# bd950_interface.net
KiCad netlist of a schematic drawn in EAGLE
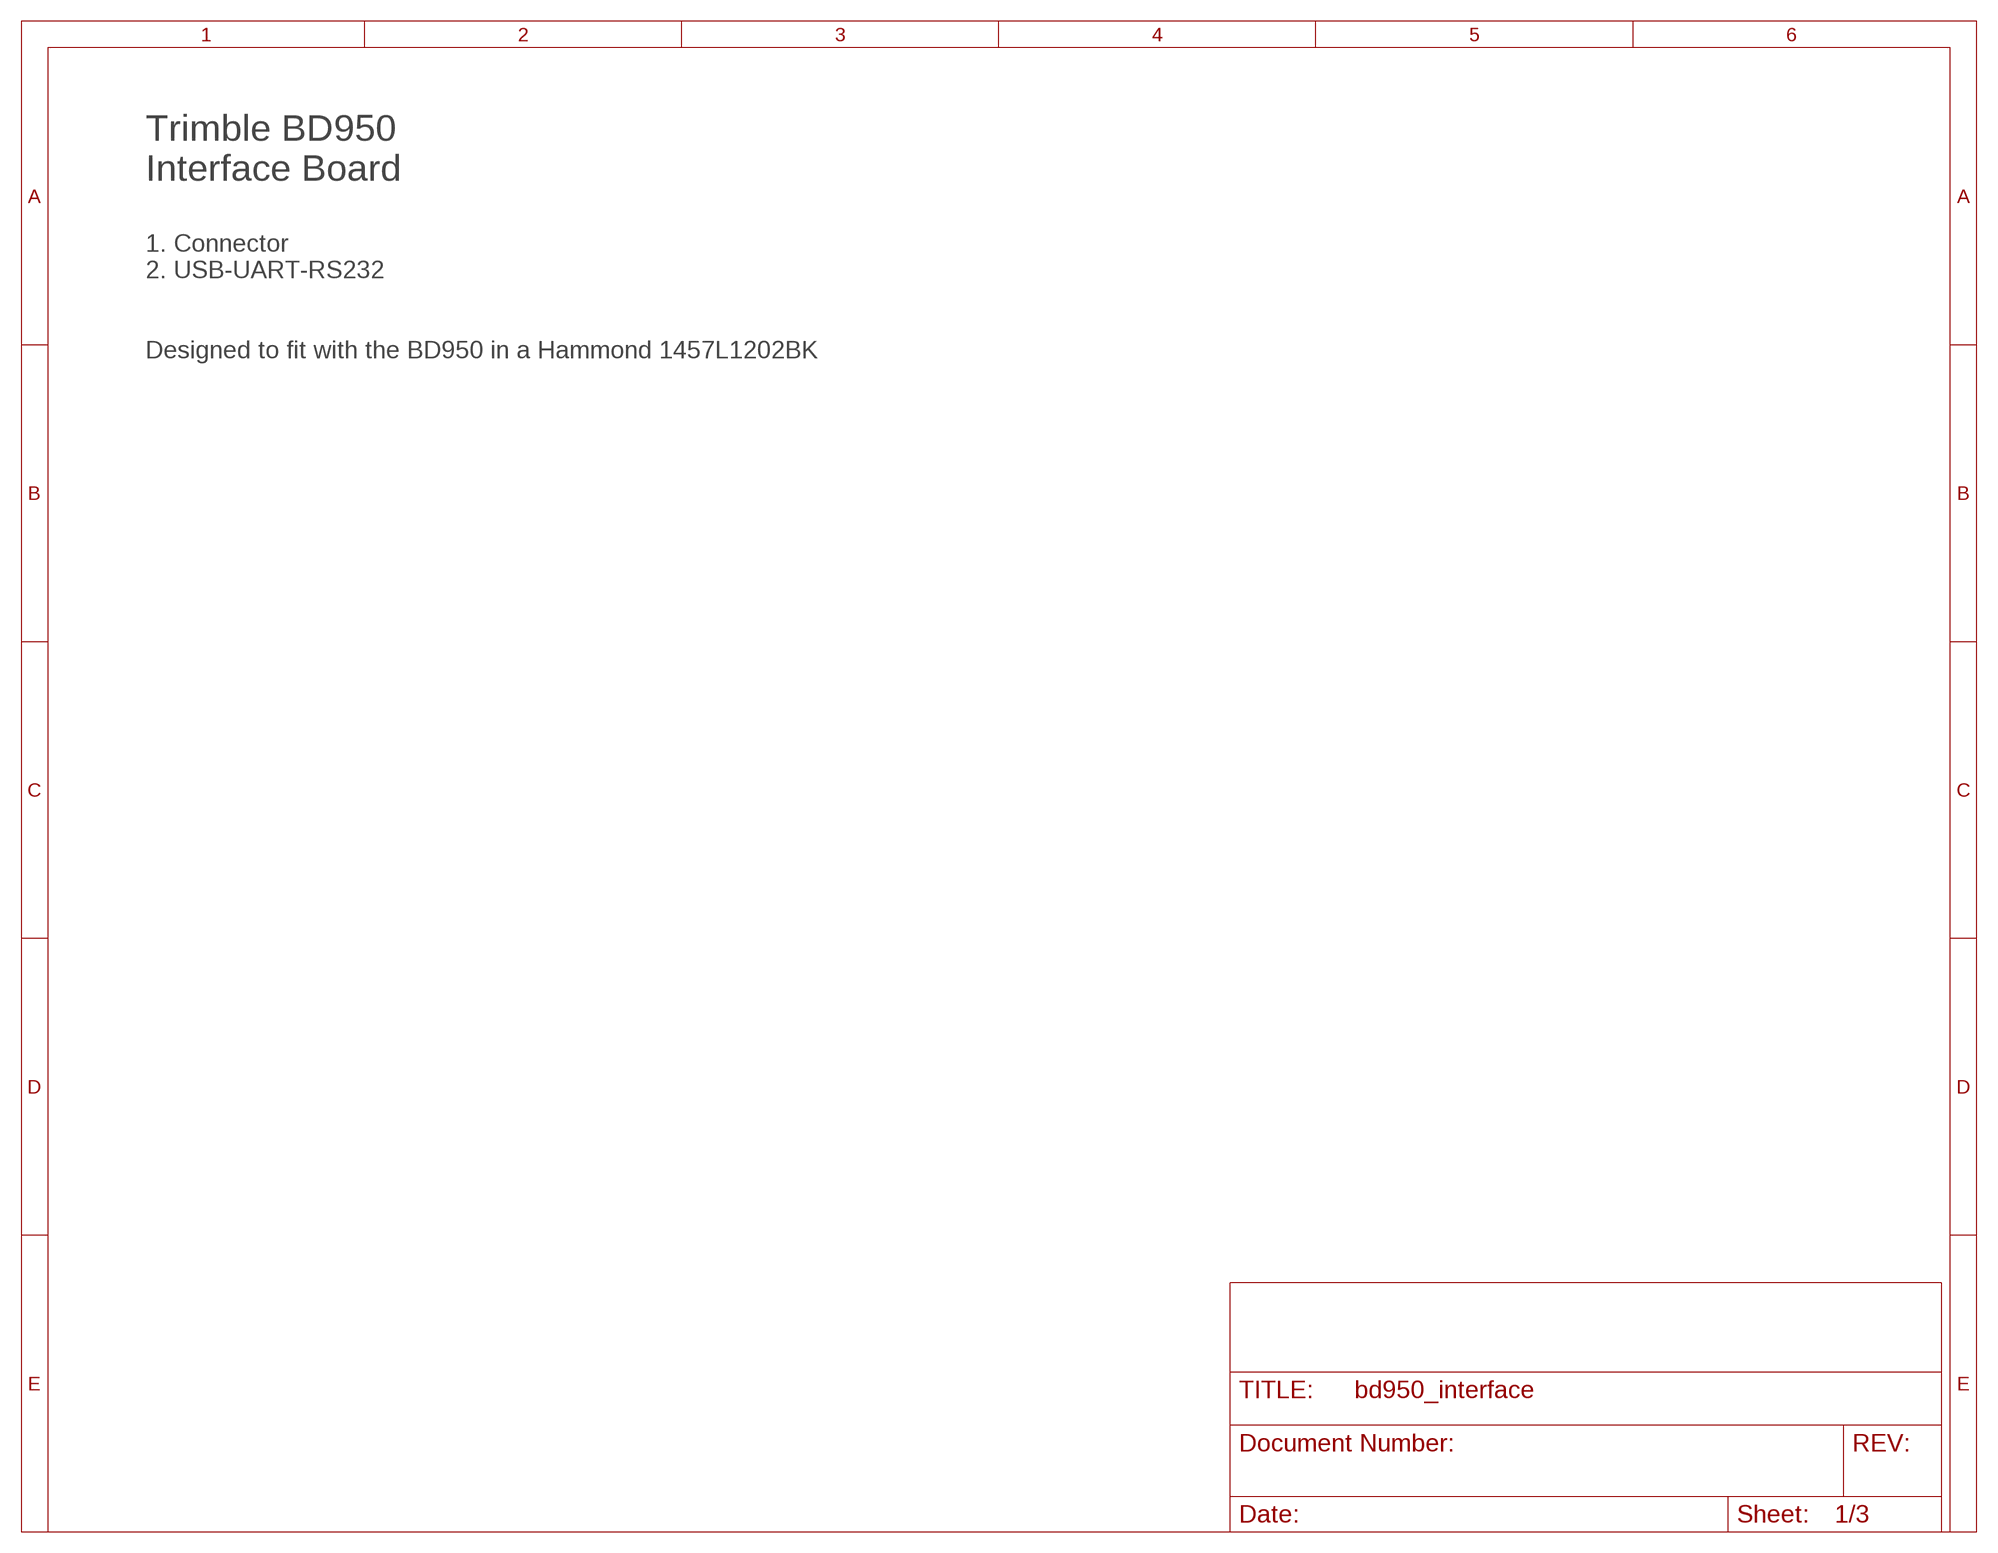
[diagram p0: schematic, sheet 1]
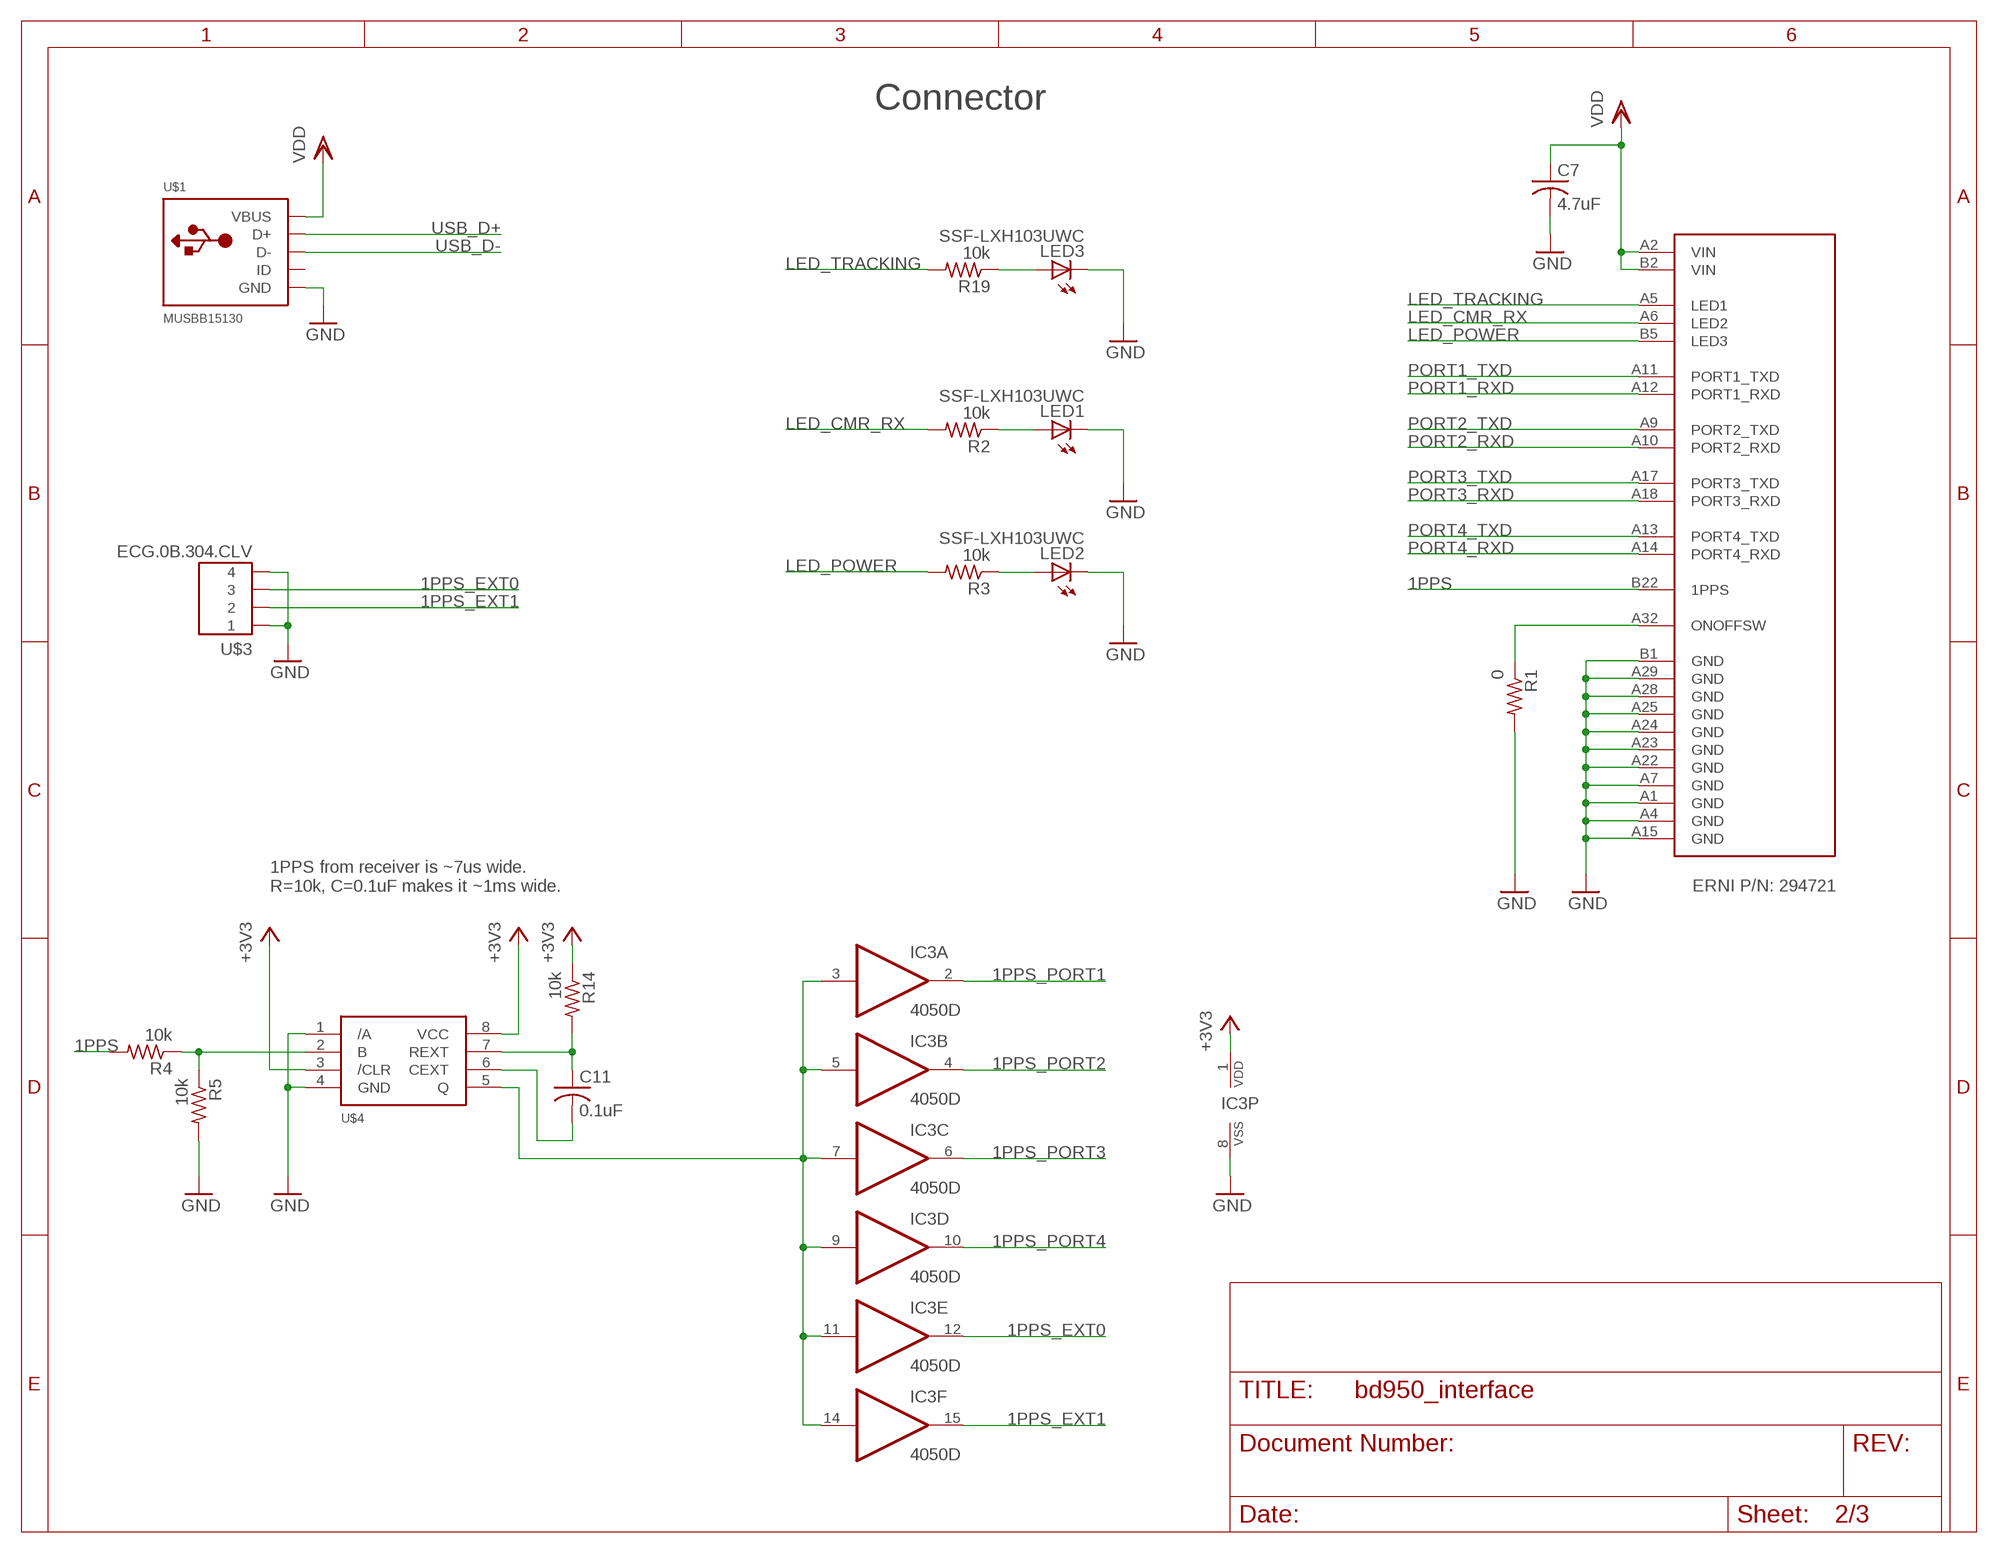
[diagram p1: schematic, sheet 2]
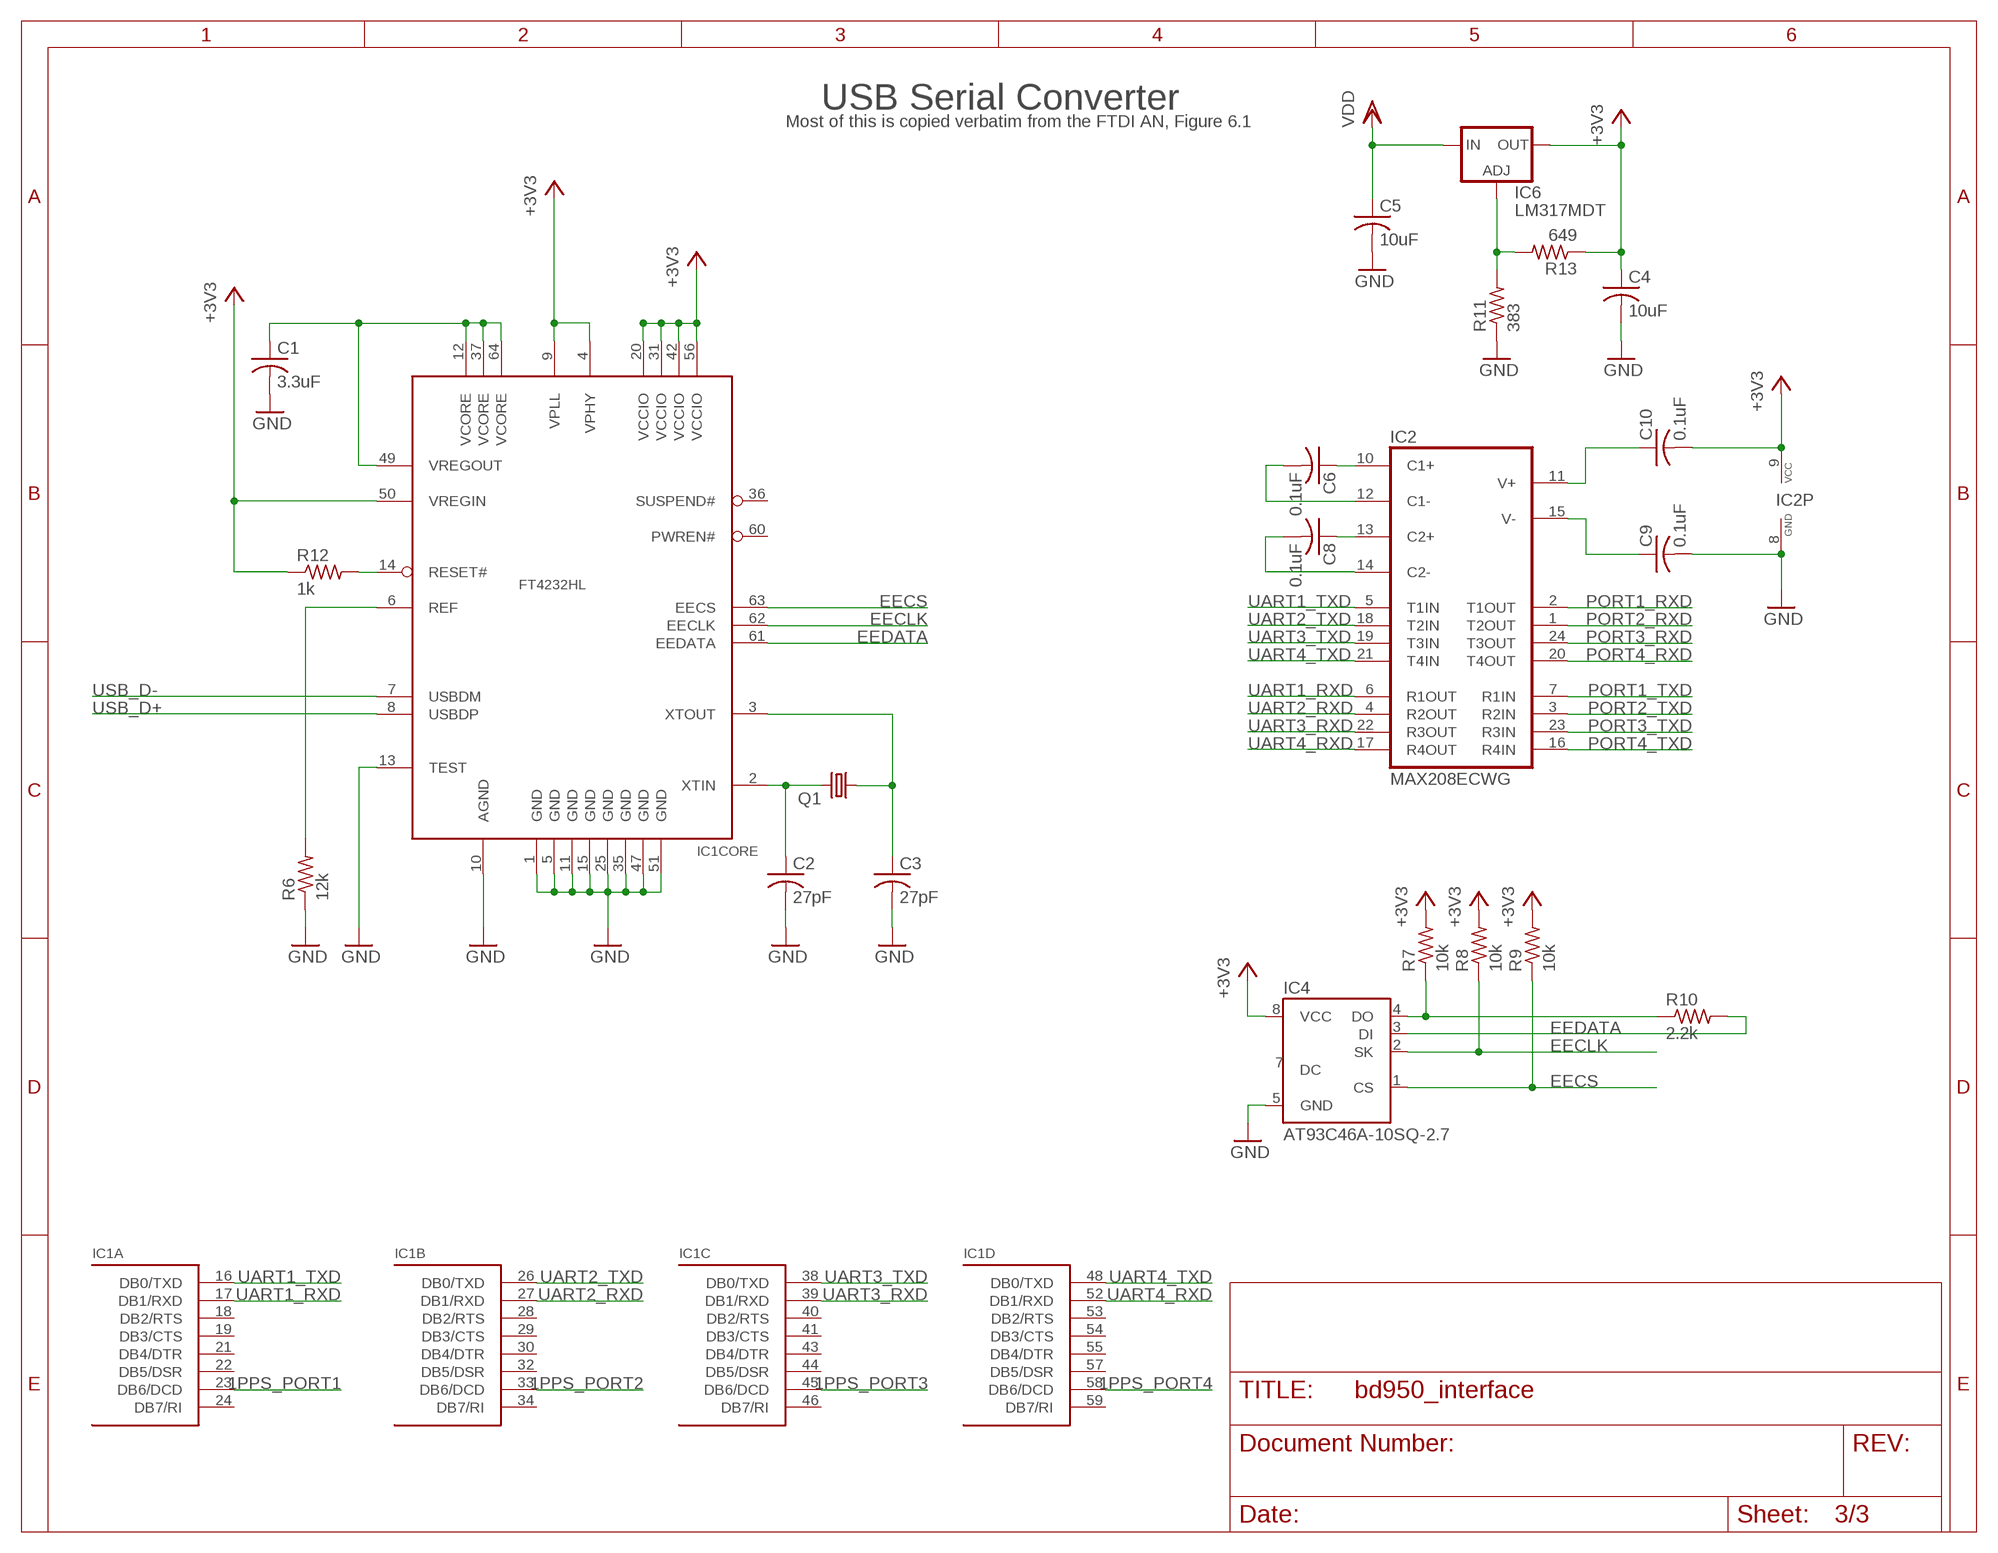
[diagram p2: schematic, sheet 3]

(export (version "E")
  (design (tool "Eeschema 10.0.6"))
  (components
    (comp (ref "C7")
      (value "4.7uF")
      (footprint "eagle-import:C0805")
      (libsource (lib "eagle-import") (part "C-USC0805"))
    )
    (comp (ref "C11")
      (value "0.1uF")
      (footprint "eagle-import:C0603")
      (libsource (lib "eagle-import") (part "C-USC0603"))
    )
    (comp (ref "IC3")
      (value "4050D")
      (footprint "eagle-import:SO16")
      (libsource (lib "eagle-import") (part "4050D"))
    )
    (comp (ref "LED1")
      (value "SSF-LXH103UWC")
      (footprint "eagle-import:CHIP-LED0603")
      (libsource (lib "eagle-import") (part "LEDCHIP-LED0603"))
    )
    (comp (ref "LED2")
      (value "SSF-LXH103UWC")
      (footprint "eagle-import:CHIP-LED0603")
      (libsource (lib "eagle-import") (part "LEDCHIP-LED0603"))
    )
    (comp (ref "LED3")
      (value "SSF-LXH103UWC")
      (footprint "eagle-import:CHIP-LED0603")
      (libsource (lib "eagle-import") (part "LEDCHIP-LED0603"))
    )
    (comp (ref "R1")
      (value "0")
      (footprint "eagle-import:R0603")
      (libsource (lib "eagle-import") (part "R-US_R0603"))
    )
    (comp (ref "R2")
      (value "10k")
      (footprint "eagle-import:R0603")
      (libsource (lib "eagle-import") (part "R-US_R0603"))
    )
    (comp (ref "R3")
      (value "10k")
      (footprint "eagle-import:R0603")
      (libsource (lib "eagle-import") (part "R-US_R0603"))
    )
    (comp (ref "R4")
      (value "10k")
      (footprint "eagle-import:R0603")
      (libsource (lib "eagle-import") (part "R-US_R0603"))
    )
    (comp (ref "R5")
      (value "10k")
      (footprint "eagle-import:R0603")
      (libsource (lib "eagle-import") (part "R-US_R0603"))
    )
    (comp (ref "R14")
      (value "10k")
      (footprint "eagle-import:R0603")
      (libsource (lib "eagle-import") (part "R-US_R0603"))
    )
    (comp (ref "R19")
      (value "10k")
      (footprint "eagle-import:R0603")
      (libsource (lib "eagle-import") (part "R-US_R0603"))
    )
    (comp (ref "U$1")
      (value "MUSBB15130")
      (footprint "eagle-import:MUSBB15130")
      (libsource (lib "eagle-import") (part "MUSBB15130"))
    )
    (comp (ref "U$2")
      (value "294721")
      (footprint "eagle-import:TRIMBLE_BD950")
      (libsource (lib "eagle-import") (part "TRIMBLE_BD950"))
    )
    (comp (ref "U$3")
      (value "ECG.0B.304.CLV")
      (footprint "eagle-import:ECG.0B.CLV")
      (libsource (lib "eagle-import") (part "ECG.0B.CLV"))
    )
    (comp (ref "U$4")
      (value "SN74LVC1G123")
      (footprint "eagle-import:DCU_(R-PDSO-G8)")
      (libsource (lib "eagle-import") (part "SN74LVC1G123"))
    )
    (comp (ref "C1")
      (value "3.3uF")
      (footprint "eagle-import:C0603")
      (libsource (lib "eagle-import") (part "C-USC0603"))
    )
    (comp (ref "C2")
      (value "27pF")
      (footprint "eagle-import:C0603")
      (libsource (lib "eagle-import") (part "C-USC0603"))
    )
    (comp (ref "C3")
      (value "27pF")
      (footprint "eagle-import:C0603")
      (libsource (lib "eagle-import") (part "C-USC0603"))
    )
    (comp (ref "C4")
      (value "10uF")
      (footprint "eagle-import:C0805")
      (libsource (lib "eagle-import") (part "C-USC0805"))
    )
    (comp (ref "C5")
      (value "10uF")
      (footprint "eagle-import:C0805")
      (libsource (lib "eagle-import") (part "C-USC0805"))
    )
    (comp (ref "C6")
      (value "0.1uF")
      (footprint "eagle-import:C0603")
      (libsource (lib "eagle-import") (part "C-USC0603"))
    )
    (comp (ref "C8")
      (value "0.1uF")
      (footprint "eagle-import:C0603")
      (libsource (lib "eagle-import") (part "C-USC0603"))
    )
    (comp (ref "C9")
      (value "0.1uF")
      (footprint "eagle-import:C0603")
      (libsource (lib "eagle-import") (part "C-USC0603"))
    )
    (comp (ref "C10")
      (value "0.1uF")
      (footprint "eagle-import:C0603")
      (libsource (lib "eagle-import") (part "C-USC0603"))
    )
    (comp (ref "IC1")
      (value "FT4232HL")
      (footprint "eagle-import:LQFP64")
      (libsource (lib "eagle-import") (part "FT4232HL"))
    )
    (comp (ref "IC2")
      (value "MAX208ECWG")
      (footprint "eagle-import:SO24L")
      (fields (field (name "MPN") "MAX208ECWG+"))
      (libsource (lib "eagle-import") (part "MAX208ECWG"))
    )
    (comp (ref "IC4")
      (value "AT93C46A-10SQ-2.7")
      (footprint "eagle-import:SOIC8")
      (fields (field (name "MPN") "AT93C46DN-SH-B"))
      (libsource (lib "eagle-import") (part "AT93C46A-10?Q-2.7S"))
    )
    (comp (ref "IC6")
      (value "LM317MDT")
      (footprint "eagle-import:DPACK")
      (libsource (lib "eagle-import") (part "LM317?MDT"))
    )
    (comp (ref "Q1")
      (value "CRYSTALHC49S")
      (footprint "eagle-import:HC49_S")
      (libsource (lib "eagle-import") (part "CRYSTALHC49S"))
    )
    (comp (ref "R6")
      (value "12k")
      (footprint "eagle-import:R0603")
      (libsource (lib "eagle-import") (part "resistor_R-US_R0603"))
    )
    (comp (ref "R7")
      (value "10k")
      (footprint "eagle-import:R0603")
      (libsource (lib "eagle-import") (part "resistor_R-US_R0603"))
    )
    (comp (ref "R8")
      (value "10k")
      (footprint "eagle-import:R0603")
      (libsource (lib "eagle-import") (part "resistor_R-US_R0603"))
    )
    (comp (ref "R9")
      (value "10k")
      (footprint "eagle-import:R0603")
      (libsource (lib "eagle-import") (part "resistor_R-US_R0603"))
    )
    (comp (ref "R10")
      (value "2.2k")
      (footprint "eagle-import:R0603")
      (libsource (lib "eagle-import") (part "resistor_R-US_R0603"))
    )
    (comp (ref "R11")
      (value "383")
      (footprint "eagle-import:R0603")
      (libsource (lib "eagle-import") (part "resistor_R-US_R0603"))
    )
    (comp (ref "R12")
      (value "1k")
      (footprint "eagle-import:R0603")
      (libsource (lib "eagle-import") (part "resistor_R-US_R0603"))
    )
    (comp (ref "R13")
      (value "649")
      (footprint "eagle-import:R0603")
      (libsource (lib "eagle-import") (part "resistor_R-US_R0603"))
    )
  )
  (nets
    (net (code "1") (name "+3V3") (class "Default")
      (node (ref "C10") (pin "2") (pinfunction "2_2") (pintype "passive"))
      (node (ref "C4") (pin "1") (pinfunction "1_1") (pintype "passive"))
      (node (ref "IC1") (pin "20") (pinfunction "VCCIO_20") (pintype "power_in"))
      (node (ref "IC1") (pin "31") (pinfunction "VCCIO_31") (pintype "power_in"))
      (node (ref "IC1") (pin "4") (pinfunction "VPHY_4") (pintype "power_in"))
      (node (ref "IC1") (pin "42") (pinfunction "VCCIO_42") (pintype "power_in"))
      (node (ref "IC1") (pin "50") (pinfunction "VREGIN_50") (pintype "bidirectional"))
      (node (ref "IC1") (pin "56") (pinfunction "VCCIO_56") (pintype "power_in"))
      (node (ref "IC1") (pin "9") (pinfunction "VPLL_9") (pintype "power_in"))
      (node (ref "IC2") (pin "9") (pinfunction "VCC_9") (pintype "power_in"))
      (node (ref "IC3") (pin "1") (pinfunction "VDD_1") (pintype "power_in"))
      (node (ref "IC4") (pin "8") (pinfunction "VCC_8") (pintype "power_in"))
      (node (ref "IC6") (pin "4") (pinfunction "OUT_4") (pintype "passive"))
      (node (ref "R12") (pin "1") (pinfunction "1_1") (pintype "passive"))
      (node (ref "R13") (pin "1") (pinfunction "1_1") (pintype "passive"))
      (node (ref "R14") (pin "1") (pinfunction "1_1") (pintype "passive"))
      (node (ref "R7") (pin "2") (pinfunction "2_2") (pintype "passive"))
      (node (ref "R8") (pin "2") (pinfunction "2_2") (pintype "passive"))
      (node (ref "R9") (pin "2") (pinfunction "2_2") (pintype "passive"))
      (node (ref "U$4") (pin "3") (pinfunction "/CLR_3") (pintype "bidirectional"))
      (node (ref "U$4") (pin "8") (pinfunction "VCC_8") (pintype "bidirectional"))
    )
    (net (code "2") (name "1PPS") (class "Default")
      (node (ref "R4") (pin "2") (pinfunction "2_2") (pintype "passive"))
      (node (ref "U$2") (pin "B22") (pinfunction "1PPS_B22") (pintype "bidirectional"))
    )
    (net (code "3") (name "1PPS_EXT0") (class "Default")
      (node (ref "IC3") (pin "12") (pinfunction "O_12") (pintype "output"))
      (node (ref "U$3") (pin "P$4") (pinfunction "3_P$4") (pintype "passive"))
    )
    (net (code "4") (name "1PPS_EXT1") (class "Default")
      (node (ref "IC3") (pin "15") (pinfunction "O_15") (pintype "output"))
      (node (ref "U$3") (pin "P$3") (pinfunction "2_P$3") (pintype "passive"))
    )
    (net (code "5") (name "1PPS_PORT1") (class "Default")
      (node (ref "IC1") (pin "23") (pinfunction "DB6/DCD_23") (pintype "bidirectional"))
      (node (ref "IC3") (pin "2") (pinfunction "O_2") (pintype "output"))
    )
    (net (code "6") (name "1PPS_PORT2") (class "Default")
      (node (ref "IC1") (pin "33") (pinfunction "DB6/DCD_33") (pintype "bidirectional"))
      (node (ref "IC3") (pin "4") (pinfunction "O_4") (pintype "output"))
    )
    (net (code "7") (name "1PPS_PORT3") (class "Default")
      (node (ref "IC1") (pin "45") (pinfunction "DB6/DCD_45") (pintype "bidirectional"))
      (node (ref "IC3") (pin "6") (pinfunction "O_6") (pintype "output"))
    )
    (net (code "8") (name "1PPS_PORT4") (class "Default")
      (node (ref "IC1") (pin "58") (pinfunction "DB6/DCD_58") (pintype "bidirectional"))
      (node (ref "IC3") (pin "10") (pinfunction "O_10") (pintype "output"))
    )
    (net (code "9") (name "EECLK") (class "Default")
      (node (ref "IC1") (pin "62") (pinfunction "EECLK_62") (pintype "output"))
      (node (ref "IC4") (pin "2") (pinfunction "SK_2") (pintype "input"))
      (node (ref "R8") (pin "1") (pinfunction "1_1") (pintype "passive"))
    )
    (net (code "10") (name "EECS") (class "Default")
      (node (ref "IC1") (pin "63") (pinfunction "EECS_63") (pintype "bidirectional"))
      (node (ref "IC4") (pin "1") (pinfunction "CS_1") (pintype "input"))
      (node (ref "R9") (pin "1") (pinfunction "1_1") (pintype "passive"))
    )
    (net (code "11") (name "EEDATA") (class "Default")
      (node (ref "IC1") (pin "61") (pinfunction "EEDATA_61") (pintype "bidirectional"))
      (node (ref "IC4") (pin "3") (pinfunction "DI_3") (pintype "input"))
      (node (ref "R10") (pin "2") (pinfunction "2_2") (pintype "passive"))
    )
    (net (code "12") (name "GND") (class "Default")
      (node (ref "C1") (pin "2") (pinfunction "2_2") (pintype "passive"))
      (node (ref "C2") (pin "2") (pinfunction "2_2") (pintype "passive"))
      (node (ref "C3") (pin "2") (pinfunction "2_2") (pintype "passive"))
      (node (ref "C4") (pin "2") (pinfunction "2_2") (pintype "passive"))
      (node (ref "C5") (pin "2") (pinfunction "2_2") (pintype "passive"))
      (node (ref "C7") (pin "2") (pinfunction "2_2") (pintype "passive"))
      (node (ref "C9") (pin "2") (pinfunction "2_2") (pintype "passive"))
      (node (ref "IC1") (pin "1") (pinfunction "GND_1") (pintype "power_in"))
      (node (ref "IC1") (pin "10") (pinfunction "AGND_10") (pintype "power_in"))
      (node (ref "IC1") (pin "11") (pinfunction "GND_11") (pintype "power_in"))
      (node (ref "IC1") (pin "13") (pinfunction "TEST_13") (pintype "input"))
      (node (ref "IC1") (pin "15") (pinfunction "GND_15") (pintype "power_in"))
      (node (ref "IC1") (pin "25") (pinfunction "GND_25") (pintype "power_in"))
      (node (ref "IC1") (pin "35") (pinfunction "GND_35") (pintype "power_in"))
      (node (ref "IC1") (pin "47") (pinfunction "GND_47") (pintype "power_in"))
      (node (ref "IC1") (pin "5") (pinfunction "GND_5") (pintype "power_in"))
      (node (ref "IC1") (pin "51") (pinfunction "GND_51") (pintype "power_in"))
      (node (ref "IC2") (pin "8") (pinfunction "GND_8") (pintype "power_in"))
      (node (ref "IC3") (pin "8") (pinfunction "VSS_8") (pintype "power_in"))
      (node (ref "IC4") (pin "5") (pinfunction "GND_5") (pintype "power_in"))
      (node (ref "LED1") (pin "C") (pinfunction "C_C") (pintype "passive"))
      (node (ref "LED2") (pin "C") (pinfunction "C_C") (pintype "passive"))
      (node (ref "LED3") (pin "C") (pinfunction "C_C") (pintype "passive"))
      (node (ref "R1") (pin "2") (pinfunction "2_2") (pintype "passive"))
      (node (ref "R11") (pin "1") (pinfunction "1_1") (pintype "passive"))
      (node (ref "R5") (pin "2") (pinfunction "2_2") (pintype "passive"))
      (node (ref "R6") (pin "1") (pinfunction "1_1") (pintype "passive"))
      (node (ref "U$1") (pin "5") (pinfunction "GND_5") (pintype "power_in"))
      (node (ref "U$2") (pin "A1") (pinfunction "GND_A1") (pintype "bidirectional"))
      (node (ref "U$2") (pin "A15") (pinfunction "GND_A15") (pintype "bidirectional"))
      (node (ref "U$2") (pin "A22") (pinfunction "GND_A22") (pintype "bidirectional"))
      (node (ref "U$2") (pin "A23") (pinfunction "GND_A23") (pintype "bidirectional"))
      (node (ref "U$2") (pin "A24") (pinfunction "GND_A24") (pintype "bidirectional"))
      (node (ref "U$2") (pin "A25") (pinfunction "GND_A25") (pintype "bidirectional"))
      (node (ref "U$2") (pin "A28") (pinfunction "GND_A28") (pintype "bidirectional"))
      (node (ref "U$2") (pin "A29") (pinfunction "GND_A29") (pintype "bidirectional"))
      (node (ref "U$2") (pin "A4") (pinfunction "GND_A4") (pintype "bidirectional"))
      (node (ref "U$2") (pin "A7") (pinfunction "GND_A7") (pintype "bidirectional"))
      (node (ref "U$2") (pin "B1") (pinfunction "GND_B1") (pintype "bidirectional"))
      (node (ref "U$3") (pin "P$1") (pinfunction "4_P$1") (pintype "passive"))
      (node (ref "U$3") (pin "P$2") (pinfunction "1_P$2") (pintype "passive"))
      (node (ref "U$4") (pin "1") (pinfunction "/A_1") (pintype "bidirectional"))
      (node (ref "U$4") (pin "4") (pinfunction "GND_4") (pintype "bidirectional"))
    )
    (net (code "13") (name "LED_CMR_RX") (class "Default")
      (node (ref "R2") (pin "2") (pinfunction "2_2") (pintype "passive"))
      (node (ref "U$2") (pin "A6") (pinfunction "LED2_A6") (pintype "bidirectional"))
    )
    (net (code "14") (name "LED_POWER") (class "Default")
      (node (ref "R3") (pin "2") (pinfunction "2_2") (pintype "passive"))
      (node (ref "U$2") (pin "B5") (pinfunction "LED3_B5") (pintype "bidirectional"))
    )
    (net (code "15") (name "LED_TRACKING") (class "Default")
      (node (ref "R19") (pin "2") (pinfunction "2_2") (pintype "passive"))
      (node (ref "U$2") (pin "A5") (pinfunction "LED1_A5") (pintype "bidirectional"))
    )
    (net (code "16") (name "Net-(IC1D-REF)") (class "Default")
      (node (ref "IC1") (pin "6") (pinfunction "REF_6") (pintype "input"))
      (node (ref "R6") (pin "2") (pinfunction "2_2") (pintype "passive"))
    )
    (net (code "17") (name "Net-(IC1D-RESET#)") (class "Default")
      (node (ref "IC1") (pin "14") (pinfunction "RESET#_14") (pintype "input"))
      (node (ref "R12") (pin "2") (pinfunction "2_2") (pintype "passive"))
    )
    (net (code "18") (name "Net-(IC1D-VREGOUT)") (class "Default")
      (node (ref "C1") (pin "1") (pinfunction "1_1") (pintype "passive"))
      (node (ref "IC1") (pin "12") (pinfunction "VCORE_12") (pintype "power_in"))
      (node (ref "IC1") (pin "37") (pinfunction "VCORE_37") (pintype "power_in"))
      (node (ref "IC1") (pin "49") (pinfunction "VREGOUT_49") (pintype "output"))
      (node (ref "IC1") (pin "64") (pinfunction "VCORE_64") (pintype "power_in"))
    )
    (net (code "19") (name "Net-(IC1D-XTIN)") (class "Default")
      (node (ref "C2") (pin "1") (pinfunction "1_1") (pintype "passive"))
      (node (ref "IC1") (pin "2") (pinfunction "XTIN_2") (pintype "input"))
      (node (ref "Q1") (pin "2") (pinfunction "2_2") (pintype "passive"))
    )
    (net (code "20") (name "Net-(IC1D-XTOUT)") (class "Default")
      (node (ref "C3") (pin "1") (pinfunction "1_1") (pintype "passive"))
      (node (ref "IC1") (pin "3") (pinfunction "XTOUT_3") (pintype "output"))
      (node (ref "Q1") (pin "1") (pinfunction "1_1") (pintype "passive"))
    )
    (net (code "21") (name "Net-(IC2A-C1+)") (class "Default")
      (node (ref "C6") (pin "1") (pinfunction "1_1") (pintype "passive"))
      (node (ref "IC2") (pin "10") (pinfunction "C1+_10") (pintype "bidirectional"))
    )
    (net (code "22") (name "Net-(IC2A-C1-)") (class "Default")
      (node (ref "C6") (pin "2") (pinfunction "2_2") (pintype "passive"))
      (node (ref "IC2") (pin "12") (pinfunction "C1-_12") (pintype "bidirectional"))
    )
    (net (code "23") (name "Net-(IC2A-C2+)") (class "Default")
      (node (ref "C8") (pin "1") (pinfunction "1_1") (pintype "passive"))
      (node (ref "IC2") (pin "13") (pinfunction "C2+_13") (pintype "bidirectional"))
    )
    (net (code "24") (name "Net-(IC2A-C2-)") (class "Default")
      (node (ref "C8") (pin "2") (pinfunction "2_2") (pintype "passive"))
      (node (ref "IC2") (pin "14") (pinfunction "C2-_14") (pintype "bidirectional"))
    )
    (net (code "25") (name "Net-(IC2A-V+)") (class "Default")
      (node (ref "C10") (pin "1") (pinfunction "1_1") (pintype "passive"))
      (node (ref "IC2") (pin "11") (pinfunction "V+_11") (pintype "bidirectional"))
    )
    (net (code "26") (name "Net-(IC2A-V-)") (class "Default")
      (node (ref "C9") (pin "1") (pinfunction "1_1") (pintype "passive"))
      (node (ref "IC2") (pin "15") (pinfunction "V-_15") (pintype "bidirectional"))
    )
    (net (code "27") (name "Net-(IC3A-I)") (class "Default")
      (node (ref "IC3") (pin "11") (pinfunction "I_11") (pintype "input"))
      (node (ref "IC3") (pin "14") (pinfunction "I_14") (pintype "input"))
      (node (ref "IC3") (pin "3") (pinfunction "I_3") (pintype "input"))
      (node (ref "IC3") (pin "5") (pinfunction "I_5") (pintype "input"))
      (node (ref "IC3") (pin "7") (pinfunction "I_7") (pintype "input"))
      (node (ref "IC3") (pin "9") (pinfunction "I_9") (pintype "input"))
      (node (ref "U$4") (pin "5") (pinfunction "Q_5") (pintype "bidirectional"))
    )
    (net (code "28") (name "Net-(IC4-DO)") (class "Default")
      (node (ref "IC4") (pin "4") (pinfunction "DO_4") (pintype "output"))
      (node (ref "R10") (pin "1") (pinfunction "1_1") (pintype "passive"))
      (node (ref "R7") (pin "1") (pinfunction "1_1") (pintype "passive"))
    )
    (net (code "29") (name "Net-(IC6-ADJ)") (class "Default")
      (node (ref "IC6") (pin "1") (pinfunction "ADJ_1") (pintype "input"))
      (node (ref "R11") (pin "2") (pinfunction "2_2") (pintype "passive"))
      (node (ref "R13") (pin "2") (pinfunction "2_2") (pintype "passive"))
    )
    (net (code "30") (name "Net-(LED1-PadA)") (class "Default")
      (node (ref "LED1") (pin "A") (pinfunction "A_A") (pintype "passive"))
      (node (ref "R2") (pin "1") (pinfunction "1_1") (pintype "passive"))
    )
    (net (code "31") (name "Net-(LED2-PadA)") (class "Default")
      (node (ref "LED2") (pin "A") (pinfunction "A_A") (pintype "passive"))
      (node (ref "R3") (pin "1") (pinfunction "1_1") (pintype "passive"))
    )
    (net (code "32") (name "Net-(LED3-PadA)") (class "Default")
      (node (ref "LED3") (pin "A") (pinfunction "A_A") (pintype "passive"))
      (node (ref "R19") (pin "1") (pinfunction "1_1") (pintype "passive"))
    )
    (net (code "33") (name "Net-(U$2-ONOFFSW)") (class "Default")
      (node (ref "R1") (pin "1") (pinfunction "1_1") (pintype "passive"))
      (node (ref "U$2") (pin "A32") (pinfunction "ONOFFSW_A32") (pintype "bidirectional"))
    )
    (net (code "34") (name "Net-(U$4-B)") (class "Default")
      (node (ref "R4") (pin "1") (pinfunction "1_1") (pintype "passive"))
      (node (ref "R5") (pin "1") (pinfunction "1_1") (pintype "passive"))
      (node (ref "U$4") (pin "2") (pinfunction "B_2") (pintype "bidirectional"))
    )
    (net (code "35") (name "Net-(U$4-CEXT)") (class "Default")
      (node (ref "C11") (pin "2") (pinfunction "2_2") (pintype "passive"))
      (node (ref "U$4") (pin "6") (pinfunction "CEXT_6") (pintype "bidirectional"))
    )
    (net (code "36") (name "Net-(U$4-REXT)") (class "Default")
      (node (ref "C11") (pin "1") (pinfunction "1_1") (pintype "passive"))
      (node (ref "R14") (pin "2") (pinfunction "2_2") (pintype "passive"))
      (node (ref "U$4") (pin "7") (pinfunction "REXT_7") (pintype "bidirectional"))
    )
    (net (code "37") (name "PORT1_RXD") (class "Default")
      (node (ref "IC2") (pin "2") (pinfunction "T1OUT_2") (pintype "output"))
      (node (ref "U$2") (pin "A12") (pinfunction "PORT1_RXD_A12") (pintype "bidirectional"))
    )
    (net (code "38") (name "PORT1_TXD") (class "Default")
      (node (ref "IC2") (pin "7") (pinfunction "R1IN_7") (pintype "input"))
      (node (ref "U$2") (pin "A11") (pinfunction "PORT1_TXD_A11") (pintype "bidirectional"))
    )
    (net (code "39") (name "PORT2_RXD") (class "Default")
      (node (ref "IC2") (pin "1") (pinfunction "T2OUT_1") (pintype "output"))
      (node (ref "U$2") (pin "A10") (pinfunction "PORT2_RXD_A10") (pintype "bidirectional"))
    )
    (net (code "40") (name "PORT2_TXD") (class "Default")
      (node (ref "IC2") (pin "3") (pinfunction "R2IN_3") (pintype "input"))
      (node (ref "U$2") (pin "A9") (pinfunction "PORT2_TXD_A9") (pintype "bidirectional"))
    )
    (net (code "41") (name "PORT3_RXD") (class "Default")
      (node (ref "IC2") (pin "24") (pinfunction "T3OUT_24") (pintype "output"))
      (node (ref "U$2") (pin "A18") (pinfunction "PORT3_RXD_A18") (pintype "bidirectional"))
    )
    (net (code "42") (name "PORT3_TXD") (class "Default")
      (node (ref "IC2") (pin "23") (pinfunction "R3IN_23") (pintype "input"))
      (node (ref "U$2") (pin "A17") (pinfunction "PORT3_TXD_A17") (pintype "bidirectional"))
    )
    (net (code "43") (name "PORT4_RXD") (class "Default")
      (node (ref "IC2") (pin "20") (pinfunction "T4OUT_20") (pintype "output"))
      (node (ref "U$2") (pin "A14") (pinfunction "PORT4_RXD_A14") (pintype "bidirectional"))
    )
    (net (code "44") (name "PORT4_TXD") (class "Default")
      (node (ref "IC2") (pin "16") (pinfunction "R4IN_16") (pintype "input"))
      (node (ref "U$2") (pin "A13") (pinfunction "PORT4_TXD_A13") (pintype "bidirectional"))
    )
    (net (code "45") (name "UART1_RXD") (class "Default")
      (node (ref "IC1") (pin "17") (pinfunction "DB1/RXD_17") (pintype "bidirectional"))
      (node (ref "IC2") (pin "6") (pinfunction "R1OUT_6") (pintype "output"))
    )
    (net (code "46") (name "UART1_TXD") (class "Default")
      (node (ref "IC1") (pin "16") (pinfunction "DB0/TXD_16") (pintype "bidirectional"))
      (node (ref "IC2") (pin "5") (pinfunction "T1IN_5") (pintype "input"))
    )
    (net (code "47") (name "UART2_RXD") (class "Default")
      (node (ref "IC1") (pin "27") (pinfunction "DB1/RXD_27") (pintype "bidirectional"))
      (node (ref "IC2") (pin "4") (pinfunction "R2OUT_4") (pintype "output"))
    )
    (net (code "48") (name "UART2_TXD") (class "Default")
      (node (ref "IC1") (pin "26") (pinfunction "DB0/TXD_26") (pintype "bidirectional"))
      (node (ref "IC2") (pin "18") (pinfunction "T2IN_18") (pintype "input"))
    )
    (net (code "49") (name "UART3_RXD") (class "Default")
      (node (ref "IC1") (pin "39") (pinfunction "DB1/RXD_39") (pintype "bidirectional"))
      (node (ref "IC2") (pin "22") (pinfunction "R3OUT_22") (pintype "output"))
    )
    (net (code "50") (name "UART3_TXD") (class "Default")
      (node (ref "IC1") (pin "38") (pinfunction "DB0/TXD_38") (pintype "bidirectional"))
      (node (ref "IC2") (pin "19") (pinfunction "T3IN_19") (pintype "input"))
    )
    (net (code "51") (name "UART4_RXD") (class "Default")
      (node (ref "IC1") (pin "52") (pinfunction "DB1/RXD_52") (pintype "bidirectional"))
      (node (ref "IC2") (pin "17") (pinfunction "R4OUT_17") (pintype "output"))
    )
    (net (code "52") (name "UART4_TXD") (class "Default")
      (node (ref "IC1") (pin "48") (pinfunction "DB0/TXD_48") (pintype "bidirectional"))
      (node (ref "IC2") (pin "21") (pinfunction "T4IN_21") (pintype "input"))
    )
    (net (code "53") (name "USB_D+") (class "Default")
      (node (ref "IC1") (pin "8") (pinfunction "USBDP_8") (pintype "input"))
      (node (ref "U$1") (pin "3") (pinfunction "D+_3") (pintype "bidirectional"))
    )
    (net (code "54") (name "USB_D-") (class "Default")
      (node (ref "IC1") (pin "7") (pinfunction "USBDM_7") (pintype "input"))
      (node (ref "U$1") (pin "2") (pinfunction "D-_2") (pintype "bidirectional"))
    )
    (net (code "55") (name "VDD") (class "Default")
      (node (ref "C5") (pin "1") (pinfunction "1_1") (pintype "passive"))
      (node (ref "C7") (pin "1") (pinfunction "1_1") (pintype "passive"))
      (node (ref "IC6") (pin "3") (pinfunction "IN_3") (pintype "input"))
      (node (ref "U$1") (pin "1") (pinfunction "VBUS_1") (pintype "power_in"))
      (node (ref "U$2") (pin "A2") (pinfunction "VIN_A2") (pintype "bidirectional"))
      (node (ref "U$2") (pin "B2") (pinfunction "VIN_B2") (pintype "bidirectional"))
    )
    (net (code "56") (name "unconnected-(IC1A-DB2{slash}RTS-Pad18)") (class "Default")
      (node (ref "IC1") (pin "18") (pinfunction "DB2/RTS_18") (pintype "bidirectional"))
    )
    (net (code "57") (name "unconnected-(IC1A-DB3{slash}CTS-Pad19)") (class "Default")
      (node (ref "IC1") (pin "19") (pinfunction "DB3/CTS_19") (pintype "bidirectional"))
    )
    (net (code "58") (name "unconnected-(IC1A-DB4{slash}DTR-Pad21)") (class "Default")
      (node (ref "IC1") (pin "21") (pinfunction "DB4/DTR_21") (pintype "bidirectional"))
    )
    (net (code "59") (name "unconnected-(IC1A-DB5{slash}DSR-Pad22)") (class "Default")
      (node (ref "IC1") (pin "22") (pinfunction "DB5/DSR_22") (pintype "bidirectional"))
    )
    (net (code "60") (name "unconnected-(IC1A-DB7{slash}RI-Pad24)") (class "Default")
      (node (ref "IC1") (pin "24") (pinfunction "DB7/RI_24") (pintype "bidirectional"))
    )
    (net (code "61") (name "unconnected-(IC1B-DB2{slash}RTS-Pad28)") (class "Default")
      (node (ref "IC1") (pin "28") (pinfunction "DB2/RTS_28") (pintype "bidirectional"))
    )
    (net (code "62") (name "unconnected-(IC1B-DB3{slash}CTS-Pad29)") (class "Default")
      (node (ref "IC1") (pin "29") (pinfunction "DB3/CTS_29") (pintype "bidirectional"))
    )
    (net (code "63") (name "unconnected-(IC1B-DB4{slash}DTR-Pad30)") (class "Default")
      (node (ref "IC1") (pin "30") (pinfunction "DB4/DTR_30") (pintype "bidirectional"))
    )
    (net (code "64") (name "unconnected-(IC1B-DB5{slash}DSR-Pad32)") (class "Default")
      (node (ref "IC1") (pin "32") (pinfunction "DB5/DSR_32") (pintype "bidirectional"))
    )
    (net (code "65") (name "unconnected-(IC1B-DB7{slash}RI-Pad34)") (class "Default")
      (node (ref "IC1") (pin "34") (pinfunction "DB7/RI_34") (pintype "bidirectional"))
    )
    (net (code "66") (name "unconnected-(IC1C-DB2{slash}RTS-Pad40)") (class "Default")
      (node (ref "IC1") (pin "40") (pinfunction "DB2/RTS_40") (pintype "bidirectional"))
    )
    (net (code "67") (name "unconnected-(IC1C-DB3{slash}CTS-Pad41)") (class "Default")
      (node (ref "IC1") (pin "41") (pinfunction "DB3/CTS_41") (pintype "bidirectional"))
    )
    (net (code "68") (name "unconnected-(IC1C-DB4{slash}DTR-Pad43)") (class "Default")
      (node (ref "IC1") (pin "43") (pinfunction "DB4/DTR_43") (pintype "bidirectional"))
    )
    (net (code "69") (name "unconnected-(IC1C-DB5{slash}DSR-Pad44)") (class "Default")
      (node (ref "IC1") (pin "44") (pinfunction "DB5/DSR_44") (pintype "bidirectional"))
    )
    (net (code "70") (name "unconnected-(IC1C-DB7{slash}RI-Pad46)") (class "Default")
      (node (ref "IC1") (pin "46") (pinfunction "DB7/RI_46") (pintype "bidirectional"))
    )
    (net (code "71") (name "unconnected-(IC1D-PWREN#-Pad60)") (class "Default")
      (node (ref "IC1") (pin "60") (pinfunction "PWREN#_60") (pintype "output"))
    )
    (net (code "72") (name "unconnected-(IC1D-SUSPEND#-Pad36)") (class "Default")
      (node (ref "IC1") (pin "36") (pinfunction "SUSPEND#_36") (pintype "output"))
    )
    (net (code "73") (name "unconnected-(IC1E-DB2{slash}RTS-Pad53)") (class "Default")
      (node (ref "IC1") (pin "53") (pinfunction "DB2/RTS_53") (pintype "bidirectional"))
    )
    (net (code "74") (name "unconnected-(IC1E-DB3{slash}CTS-Pad54)") (class "Default")
      (node (ref "IC1") (pin "54") (pinfunction "DB3/CTS_54") (pintype "bidirectional"))
    )
    (net (code "75") (name "unconnected-(IC1E-DB4{slash}DTR-Pad55)") (class "Default")
      (node (ref "IC1") (pin "55") (pinfunction "DB4/DTR_55") (pintype "bidirectional"))
    )
    (net (code "76") (name "unconnected-(IC1E-DB5{slash}DSR-Pad57)") (class "Default")
      (node (ref "IC1") (pin "57") (pinfunction "DB5/DSR_57") (pintype "bidirectional"))
    )
    (net (code "77") (name "unconnected-(IC1E-DB7{slash}RI-Pad59)") (class "Default")
      (node (ref "IC1") (pin "59") (pinfunction "DB7/RI_59") (pintype "bidirectional"))
    )
    (net (code "78") (name "unconnected-(IC4-DC-Pad7)") (class "Default")
      (node (ref "IC4") (pin "7") (pinfunction "DC_7") (pintype "no_connect"))
    )
    (net (code "79") (name "unconnected-(IC4-NC-Pad6)") (class "Default")
      (node (ref "IC4") (pin "6") (pinfunction "NC_6") (pintype "no_connect"))
    )
    (net (code "80") (name "unconnected-(U$1-ID-Pad4)") (class "Default")
      (node (ref "U$1") (pin "4") (pinfunction "ID_4") (pintype "bidirectional"))
    )
  )
)
